# Schemeatic_1_0.net
KiCad netlist of a schematic drawn in Altium Designer
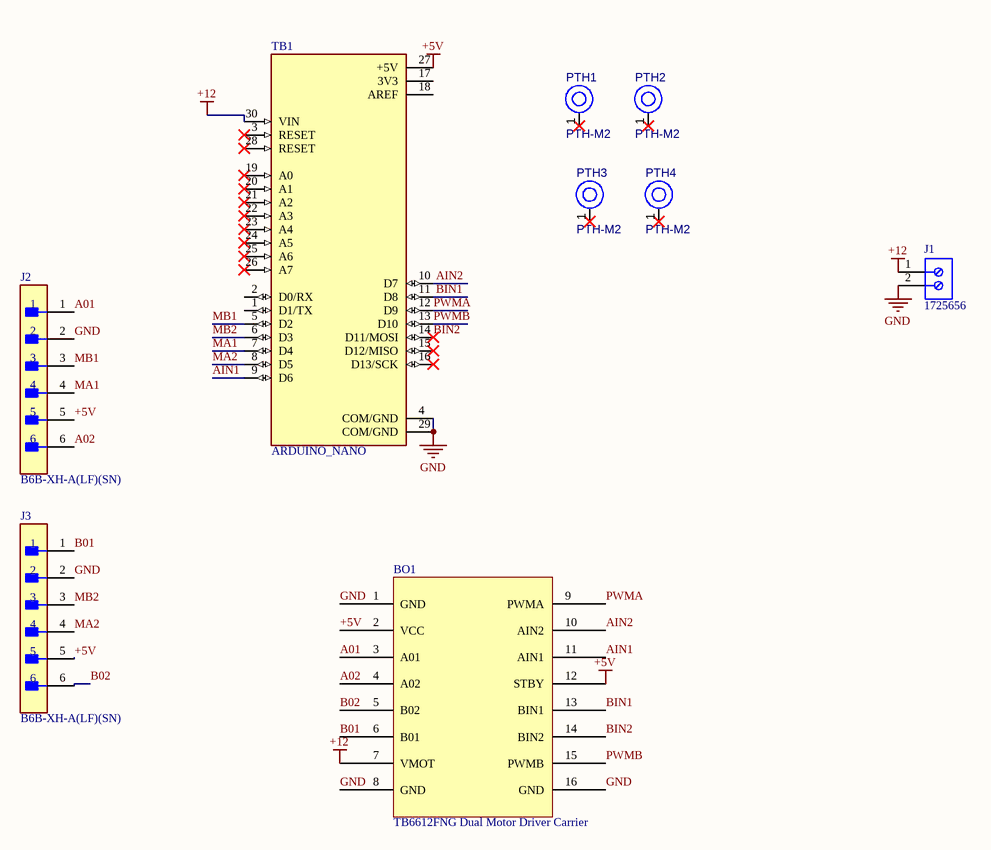
[diagram p0: Schemeatic_1_0.SchDoc]

(export (version "E")
  (design (tool "Eeschema 10.0.6"))
  (components
    (comp (ref "BO1")
      (value "TB6612FNG Dual Motor Driver Carrier")
      (footprint "DIP16 - duplicate1")
      (libsource (lib "motor_16_driver") (part "TB6612FNG_Breakout"))
    )
    (comp (ref "J1")
      (value "1725656")
      (footprint "PHOE-1725656-2")
      (description "Male Header, Pitch 2.54 mm, 1 x 2 Position, Height 9 mm, Tail Length 3.5 mm")
      (fields (field (name "MANUFACTURER") "Phoenix Contact"))
      (libsource (lib "Altium Content Vault") (part "CN-1P-F-TB2"))
    )
    (comp (ref "J2")
      (value "B6B-XH-A(LF)(SN)")
      (footprint "FP-B6B-XH-A_LF_SN-MFG")
      (description "CONN HEADER VERT 6POS 2.5MM")
      (libsource (lib "Altium Content Vault") (part "f2cb566baf1c37ab5a3b8e90bbeafd6"))
    )
    (comp (ref "J3")
      (value "B6B-XH-A(LF)(SN)")
      (footprint "FP-B6B-XH-A_LF_SN-MFG")
      (description "CONN HEADER VERT 6POS 2.5MM")
      (libsource (lib "Altium Content Vault") (part "f2cb566baf1c37ab5a3b8e90bbeafd6"))
    )
    (comp (ref "PTH1")
      (value "PTH-M2")
      (footprint "PTH-M2")
      (description "M2 Clearance (2.2 mm) Plated Through Hole, 6mm Diameter Pad")
      (fields (field (name "CREATED BY") "Robert Howie"))
      (libsource (lib "AERO3001 Spacecraft Project") (part "CMP-00003-1"))
    )
    (comp (ref "PTH2")
      (value "PTH-M2")
      (footprint "PTH-M2")
      (description "M2 Clearance (2.2 mm) Plated Through Hole, 6mm Diameter Pad")
      (fields (field (name "CREATED BY") "Robert Howie"))
      (libsource (lib "AERO3001 Spacecraft Project") (part "CMP-00003-1"))
    )
    (comp (ref "PTH3")
      (value "PTH-M2")
      (footprint "PTH-M2")
      (description "M2 Clearance (2.2 mm) Plated Through Hole, 6mm Diameter Pad")
      (fields (field (name "CREATED BY") "Robert Howie"))
      (libsource (lib "AERO3001 Spacecraft Project") (part "CMP-00003-1"))
    )
    (comp (ref "PTH4")
      (value "PTH-M2")
      (footprint "PTH-M2")
      (description "M2 Clearance (2.2 mm) Plated Through Hole, 6mm Diameter Pad")
      (fields (field (name "CREATED BY") "Robert Howie"))
      (libsource (lib "AERO3001 Spacecraft Project") (part "CMP-00003-1"))
    )
    (comp (ref "TB1")
      (value "ARDUINO_NANO")
      (footprint "SHIELD_ARDUINO_NANO")
      (description "Small, complete, and breadboard-friendly board based on the ATmega328 (Arduino Nano 3.x)")
      (fields (field (name "MP") "Arduino Nano") (field (name "MF") "Arduino"))
      (libsource (lib "ARDUINO_NANO") (part "ARDUINO_NANO"))
    )
  )
  (nets
    (net (code "1") (name "+5V") (class "Default")
      (node (ref "BO1") (pin "12") (pinfunction "STBY_12") (pintype "passive"))
      (node (ref "BO1") (pin "2") (pinfunction "VCC_2") (pintype "passive"))
      (node (ref "J2") (pin "5") (pinfunction "5_5") (pintype "passive"))
      (node (ref "J3") (pin "5") (pinfunction "5_5") (pintype "passive"))
      (node (ref "TB1") (pin "27") (pinfunction "+5V_27") (pintype "power_in"))
    )
    (net (code "2") (name "+12") (class "Default")
      (node (ref "BO1") (pin "7") (pinfunction "VMOT_7") (pintype "passive"))
      (node (ref "J1") (pin "1") (pinfunction "1_1") (pintype "passive"))
      (node (ref "TB1") (pin "30") (pinfunction "VIN_30") (pintype "input"))
    )
    (net (code "3") (name "/A01") (class "Default")
      (node (ref "BO1") (pin "3") (pinfunction "A01_3") (pintype "passive"))
      (node (ref "J2") (pin "1") (pinfunction "1_1") (pintype "passive"))
    )
    (net (code "4") (name "/A02") (class "Default")
      (node (ref "BO1") (pin "4") (pinfunction "A02_4") (pintype "passive"))
      (node (ref "J2") (pin "6") (pinfunction "6_6") (pintype "passive"))
    )
    (net (code "5") (name "/AIN1") (class "Default")
      (node (ref "BO1") (pin "11") (pinfunction "AIN1_11") (pintype "passive"))
      (node (ref "TB1") (pin "9") (pinfunction "D6_9") (pintype "bidirectional"))
    )
    (net (code "6") (name "/AIN2") (class "Default")
      (node (ref "BO1") (pin "10") (pinfunction "AIN2_10") (pintype "passive"))
      (node (ref "TB1") (pin "10") (pinfunction "D7_10") (pintype "bidirectional"))
    )
    (net (code "7") (name "/B01") (class "Default")
      (node (ref "BO1") (pin "6") (pinfunction "B01_6") (pintype "passive"))
      (node (ref "J3") (pin "1") (pinfunction "1_1") (pintype "passive"))
    )
    (net (code "8") (name "/B02") (class "Default")
      (node (ref "BO1") (pin "5") (pinfunction "B02_5") (pintype "passive"))
      (node (ref "J3") (pin "6") (pinfunction "6_6") (pintype "passive"))
    )
    (net (code "9") (name "/BIN1") (class "Default")
      (node (ref "BO1") (pin "13") (pinfunction "BIN1_13") (pintype "passive"))
      (node (ref "TB1") (pin "11") (pinfunction "D8_11") (pintype "bidirectional"))
    )
    (net (code "10") (name "/BIN2") (class "Default")
      (node (ref "BO1") (pin "14") (pinfunction "BIN2_14") (pintype "passive"))
      (node (ref "TB1") (pin "14") (pinfunction "D11/MOSI_14") (pintype "bidirectional"))
    )
    (net (code "11") (name "/MA1") (class "Default")
      (node (ref "J2") (pin "4") (pinfunction "4_4") (pintype "passive"))
      (node (ref "TB1") (pin "7") (pinfunction "D4_7") (pintype "bidirectional"))
    )
    (net (code "12") (name "/MA2") (class "Default")
      (node (ref "J3") (pin "4") (pinfunction "4_4") (pintype "passive"))
      (node (ref "TB1") (pin "8") (pinfunction "D5_8") (pintype "bidirectional"))
    )
    (net (code "13") (name "/MB1") (class "Default")
      (node (ref "J2") (pin "3") (pinfunction "3_3") (pintype "passive"))
      (node (ref "TB1") (pin "5") (pinfunction "D2_5") (pintype "bidirectional"))
    )
    (net (code "14") (name "/MB2") (class "Default")
      (node (ref "J3") (pin "3") (pinfunction "3_3") (pintype "passive"))
      (node (ref "TB1") (pin "6") (pinfunction "D3_6") (pintype "bidirectional"))
    )
    (net (code "15") (name "/PWMA") (class "Default")
      (node (ref "BO1") (pin "9") (pinfunction "PWMA_9") (pintype "passive"))
      (node (ref "TB1") (pin "12") (pinfunction "D9_12") (pintype "bidirectional"))
    )
    (net (code "16") (name "/PWMB") (class "Default")
      (node (ref "BO1") (pin "15") (pinfunction "PWMB_15") (pintype "passive"))
      (node (ref "TB1") (pin "13") (pinfunction "D10_13") (pintype "bidirectional"))
    )
    (net (code "17") (name "GND") (class "Default")
      (node (ref "BO1") (pin "1") (pinfunction "GND_1") (pintype "passive"))
      (node (ref "BO1") (pin "16") (pinfunction "GND_16") (pintype "passive"))
      (node (ref "BO1") (pin "8") (pinfunction "GND_8") (pintype "passive"))
      (node (ref "J1") (pin "2") (pinfunction "2_2") (pintype "passive"))
      (node (ref "J2") (pin "2") (pinfunction "2_2") (pintype "passive"))
      (node (ref "J3") (pin "2") (pinfunction "2_2") (pintype "passive"))
      (node (ref "TB1") (pin "29") (pinfunction "COM/GND_29") (pintype "power_in"))
      (node (ref "TB1") (pin "4") (pinfunction "COM/GND_4") (pintype "power_in"))
    )
    (net (code "18") (name "unconnected-(PTH1-H1-Pad1)") (class "Default")
      (node (ref "PTH1") (pin "1") (pinfunction "H1_1") (pintype "passive+no_connect"))
    )
    (net (code "19") (name "unconnected-(PTH2-H1-Pad1)") (class "Default")
      (node (ref "PTH2") (pin "1") (pinfunction "H1_1") (pintype "passive+no_connect"))
    )
    (net (code "20") (name "unconnected-(PTH3-H1-Pad1)") (class "Default")
      (node (ref "PTH3") (pin "1") (pinfunction "H1_1") (pintype "passive+no_connect"))
    )
    (net (code "21") (name "unconnected-(PTH4-H1-Pad1)") (class "Default")
      (node (ref "PTH4") (pin "1") (pinfunction "H1_1") (pintype "passive+no_connect"))
    )
    (net (code "22") (name "unconnected-(TB1-3V3-Pad17)") (class "Default")
      (node (ref "TB1") (pin "17") (pinfunction "3V3_17") (pintype "power_in"))
    )
    (net (code "23") (name "unconnected-(TB1-A0-Pad19)") (class "Default")
      (node (ref "TB1") (pin "19") (pinfunction "A0_19") (pintype "input+no_connect"))
    )
    (net (code "24") (name "unconnected-(TB1-A1-Pad20)") (class "Default")
      (node (ref "TB1") (pin "20") (pinfunction "A1_20") (pintype "input+no_connect"))
    )
    (net (code "25") (name "unconnected-(TB1-A2-Pad21)") (class "Default")
      (node (ref "TB1") (pin "21") (pinfunction "A2_21") (pintype "input+no_connect"))
    )
    (net (code "26") (name "unconnected-(TB1-A3-Pad22)") (class "Default")
      (node (ref "TB1") (pin "22") (pinfunction "A3_22") (pintype "input+no_connect"))
    )
    (net (code "27") (name "unconnected-(TB1-A4-Pad23)") (class "Default")
      (node (ref "TB1") (pin "23") (pinfunction "A4_23") (pintype "input+no_connect"))
    )
    (net (code "28") (name "unconnected-(TB1-A5-Pad24)") (class "Default")
      (node (ref "TB1") (pin "24") (pinfunction "A5_24") (pintype "input+no_connect"))
    )
    (net (code "29") (name "unconnected-(TB1-A6-Pad25)") (class "Default")
      (node (ref "TB1") (pin "25") (pinfunction "A6_25") (pintype "input+no_connect"))
    )
    (net (code "30") (name "unconnected-(TB1-A7-Pad26)") (class "Default")
      (node (ref "TB1") (pin "26") (pinfunction "A7_26") (pintype "input+no_connect"))
    )
    (net (code "31") (name "unconnected-(TB1-AREF-Pad18)") (class "Default")
      (node (ref "TB1") (pin "18") (pinfunction "AREF_18") (pintype "power_in"))
    )
    (net (code "32") (name "unconnected-(TB1-D0{slash}RX-Pad2)") (class "Default")
      (node (ref "TB1") (pin "2") (pinfunction "D0/RX_2") (pintype "bidirectional"))
    )
    (net (code "33") (name "unconnected-(TB1-D1{slash}TX-Pad1)") (class "Default")
      (node (ref "TB1") (pin "1") (pinfunction "D1/TX_1") (pintype "bidirectional"))
    )
    (net (code "34") (name "unconnected-(TB1-D12{slash}MISO-Pad15)") (class "Default")
      (node (ref "TB1") (pin "15") (pinfunction "D12/MISO_15") (pintype "bidirectional+no_connect"))
    )
    (net (code "35") (name "unconnected-(TB1-D13{slash}SCK-Pad16)") (class "Default")
      (node (ref "TB1") (pin "16") (pinfunction "D13/SCK_16") (pintype "bidirectional+no_connect"))
    )
    (net (code "36") (name "unconnected-(TB1-RESET-Pad3)") (class "Default")
      (node (ref "TB1") (pin "3") (pinfunction "RESET_3") (pintype "input+no_connect"))
    )
    (net (code "37") (name "unconnected-(TB1-RESET-Pad28)") (class "Default")
      (node (ref "TB1") (pin "28") (pinfunction "RESET_28") (pintype "input+no_connect"))
    )
  )
)
